# Kelompok_01_LaporanAkhir_DE2022.net
KiCad netlist of a schematic drawn in EAGLE
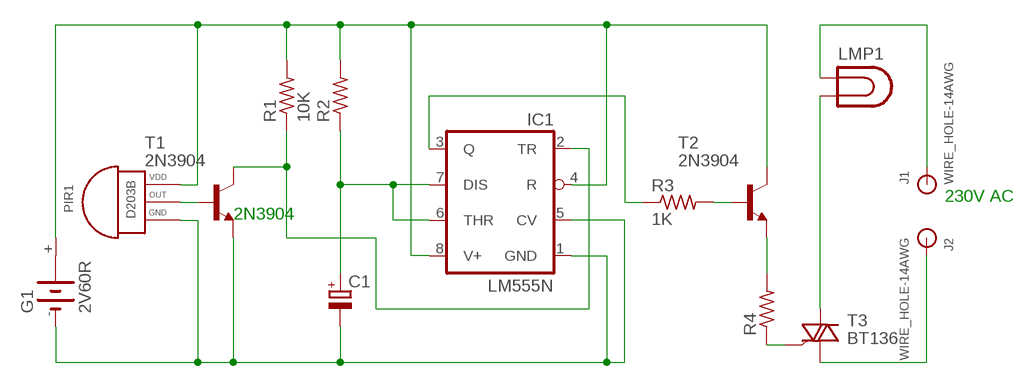
[diagram p0: schematic, sheet 1]

(export (version "E")
  (design (tool "Eeschema 10.0.6"))
  (components
    (comp (ref "C1")
      (value "CPOL-EUB45181C")
      (footprint "eagle-import:B45181C")
      (libsource (lib "eagle-import") (part "CPOL-EUB45181C"))
    )
    (comp (ref "G1")
      (value "2V60R")
      (footprint "eagle-import:2V60R")
      (libsource (lib "eagle-import") (part "2V60R"))
    )
    (comp (ref "IC1")
      (value "LM555N")
      (footprint "eagle-import:DIL08")
      (libsource (lib "eagle-import") (part "555NLM"))
    )
    (comp (ref "J1")
      (value "WIRE_HOLE-14AWG")
      (footprint "eagle-import:WIRE_HOLE-14AWG")
      (libsource (lib "eagle-import") (part "WIRE_HOLE-14AWG"))
    )
    (comp (ref "J2")
      (value "WIRE_HOLE-14AWG")
      (footprint "eagle-import:WIRE_HOLE-14AWG")
      (libsource (lib "eagle-import") (part "WIRE_HOLE-14AWG"))
    )
    (comp (ref "LMP1")
      (value "LAMP")
      (footprint "eagle-import:LDH-5R")
      (libsource (lib "eagle-import") (part "LAMP"))
    )
    (comp (ref "PIR1")
      (value "D203B")
      (footprint "eagle-import:3PIN")
      (libsource (lib "eagle-import") (part "D203B"))
    )
    (comp (ref "R1")
      (value "10K")
      (footprint "eagle-import:0204_7")
      (libsource (lib "eagle-import") (part "R-US_0204/7"))
    )
    (comp (ref "R2")
      (value "R-US_0204/7")
      (footprint "eagle-import:0204_7")
      (libsource (lib "eagle-import") (part "R-US_0204/7"))
    )
    (comp (ref "R3")
      (value "1K")
      (footprint "eagle-import:0204_7")
      (libsource (lib "eagle-import") (part "R-US_0204/7"))
    )
    (comp (ref "R4")
      (value "R-US_0204/7")
      (footprint "eagle-import:0204_7")
      (libsource (lib "eagle-import") (part "R-US_0204/7"))
    )
    (comp (ref "T1")
      (value "2N3904")
      (footprint "eagle-import:TO92")
      (libsource (lib "eagle-import") (part "2N3904"))
    )
    (comp (ref "T2")
      (value "2N3904")
      (footprint "eagle-import:TO92")
      (libsource (lib "eagle-import") (part "2N3904"))
    )
    (comp (ref "T3")
      (value "BT136")
      (footprint "eagle-import:TO220AB")
      (libsource (lib "eagle-import") (part "BT136"))
    )
  )
  (nets
    (net (code "1") (name "Net-(IC1-CV)") (class "Default")
      (node (ref "C1") (pin "-") (pinfunction "-_-") (pintype "passive"))
      (node (ref "G1") (pin "-") (pinfunction "-_-") (pintype "passive"))
      (node (ref "IC1") (pin "1") (pinfunction "GND_1") (pintype "power_in"))
      (node (ref "IC1") (pin "5") (pinfunction "CV_5") (pintype "input"))
      (node (ref "PIR1") (pin "3") (pinfunction "GND_3") (pintype "bidirectional"))
      (node (ref "T1") (pin "3") (pinfunction "E_3") (pintype "passive"))
    )
    (net (code "2") (name "Net-(IC1-DIS)") (class "Default")
      (node (ref "C1") (pin "+") (pinfunction "+_+") (pintype "passive"))
      (node (ref "IC1") (pin "6") (pinfunction "THR_6") (pintype "input"))
      (node (ref "IC1") (pin "7") (pinfunction "DIS_7") (pintype "input"))
      (node (ref "R2") (pin "1") (pinfunction "1_1") (pintype "passive"))
    )
    (net (code "3") (name "Net-(IC1-Q)") (class "Default")
      (node (ref "IC1") (pin "3") (pinfunction "Q_3") (pintype "output"))
      (node (ref "R3") (pin "1") (pinfunction "1_1") (pintype "passive"))
    )
    (net (code "4") (name "Net-(IC1-R)") (class "Default")
      (node (ref "G1") (pin "+") (pinfunction "+_+") (pintype "passive"))
      (node (ref "IC1") (pin "4") (pinfunction "R_4") (pintype "input"))
      (node (ref "IC1") (pin "8") (pinfunction "V+_8") (pintype "power_in"))
      (node (ref "PIR1") (pin "1") (pinfunction "VDD_1") (pintype "bidirectional"))
      (node (ref "R1") (pin "2") (pinfunction "2_2") (pintype "passive"))
      (node (ref "R2") (pin "2") (pinfunction "2_2") (pintype "passive"))
      (node (ref "T2") (pin "1") (pinfunction "C_1") (pintype "passive"))
    )
    (net (code "5") (name "Net-(IC1-TR)") (class "Default")
      (node (ref "IC1") (pin "2") (pinfunction "TR_2") (pintype "input"))
      (node (ref "R1") (pin "1") (pinfunction "1_1") (pintype "passive"))
      (node (ref "T1") (pin "1") (pinfunction "C_1") (pintype "passive"))
    )
    (net (code "6") (name "Net-(J1-PadP$1)") (class "Default")
      (node (ref "J1") (pin "P$1") (pinfunction "P$1_P$1") (pintype "bidirectional"))
      (node (ref "LMP1") (pin "1") (pinfunction "1_1") (pintype "passive"))
    )
    (net (code "7") (name "Net-(PIR1-OUT)") (class "Default")
      (node (ref "PIR1") (pin "2") (pinfunction "OUT_2") (pintype "bidirectional"))
      (node (ref "T1") (pin "2") (pinfunction "B_2") (pintype "passive"))
    )
    (net (code "8") (name "Net-(T2-B)") (class "Default")
      (node (ref "R3") (pin "2") (pinfunction "2_2") (pintype "passive"))
      (node (ref "T2") (pin "2") (pinfunction "B_2") (pintype "passive"))
    )
    (net (code "9") (name "Net-(T2-E)") (class "Default")
      (node (ref "R4") (pin "2") (pinfunction "2_2") (pintype "passive"))
      (node (ref "T2") (pin "3") (pinfunction "E_3") (pintype "passive"))
    )
    (net (code "10") (name "Net-(T3-A1)") (class "Default")
      (node (ref "J2") (pin "P$1") (pinfunction "P$1_P$1") (pintype "bidirectional"))
      (node (ref "T3") (pin "1") (pinfunction "A1_1") (pintype "passive"))
    )
    (net (code "11") (name "Net-(T3-A2)") (class "Default")
      (node (ref "LMP1") (pin "2") (pinfunction "2_2") (pintype "passive"))
      (node (ref "T3") (pin "2") (pinfunction "A2_2") (pintype "passive"))
    )
    (net (code "12") (name "Net-(T3-G)") (class "Default")
      (node (ref "R4") (pin "1") (pinfunction "1_1") (pintype "passive"))
      (node (ref "T3") (pin "3") (pinfunction "G_3") (pintype "passive"))
    )
    (net (code "13") (name "unconnected-(G1-+-Pad+@1)") (class "Default")
      (node (ref "G1") (pin "+@1") (pinfunction "+_+@1") (pintype "passive"))
    )
  )
)
